# Primary_MCU.net
KiCad netlist of a schematic drawn in Altium Designer
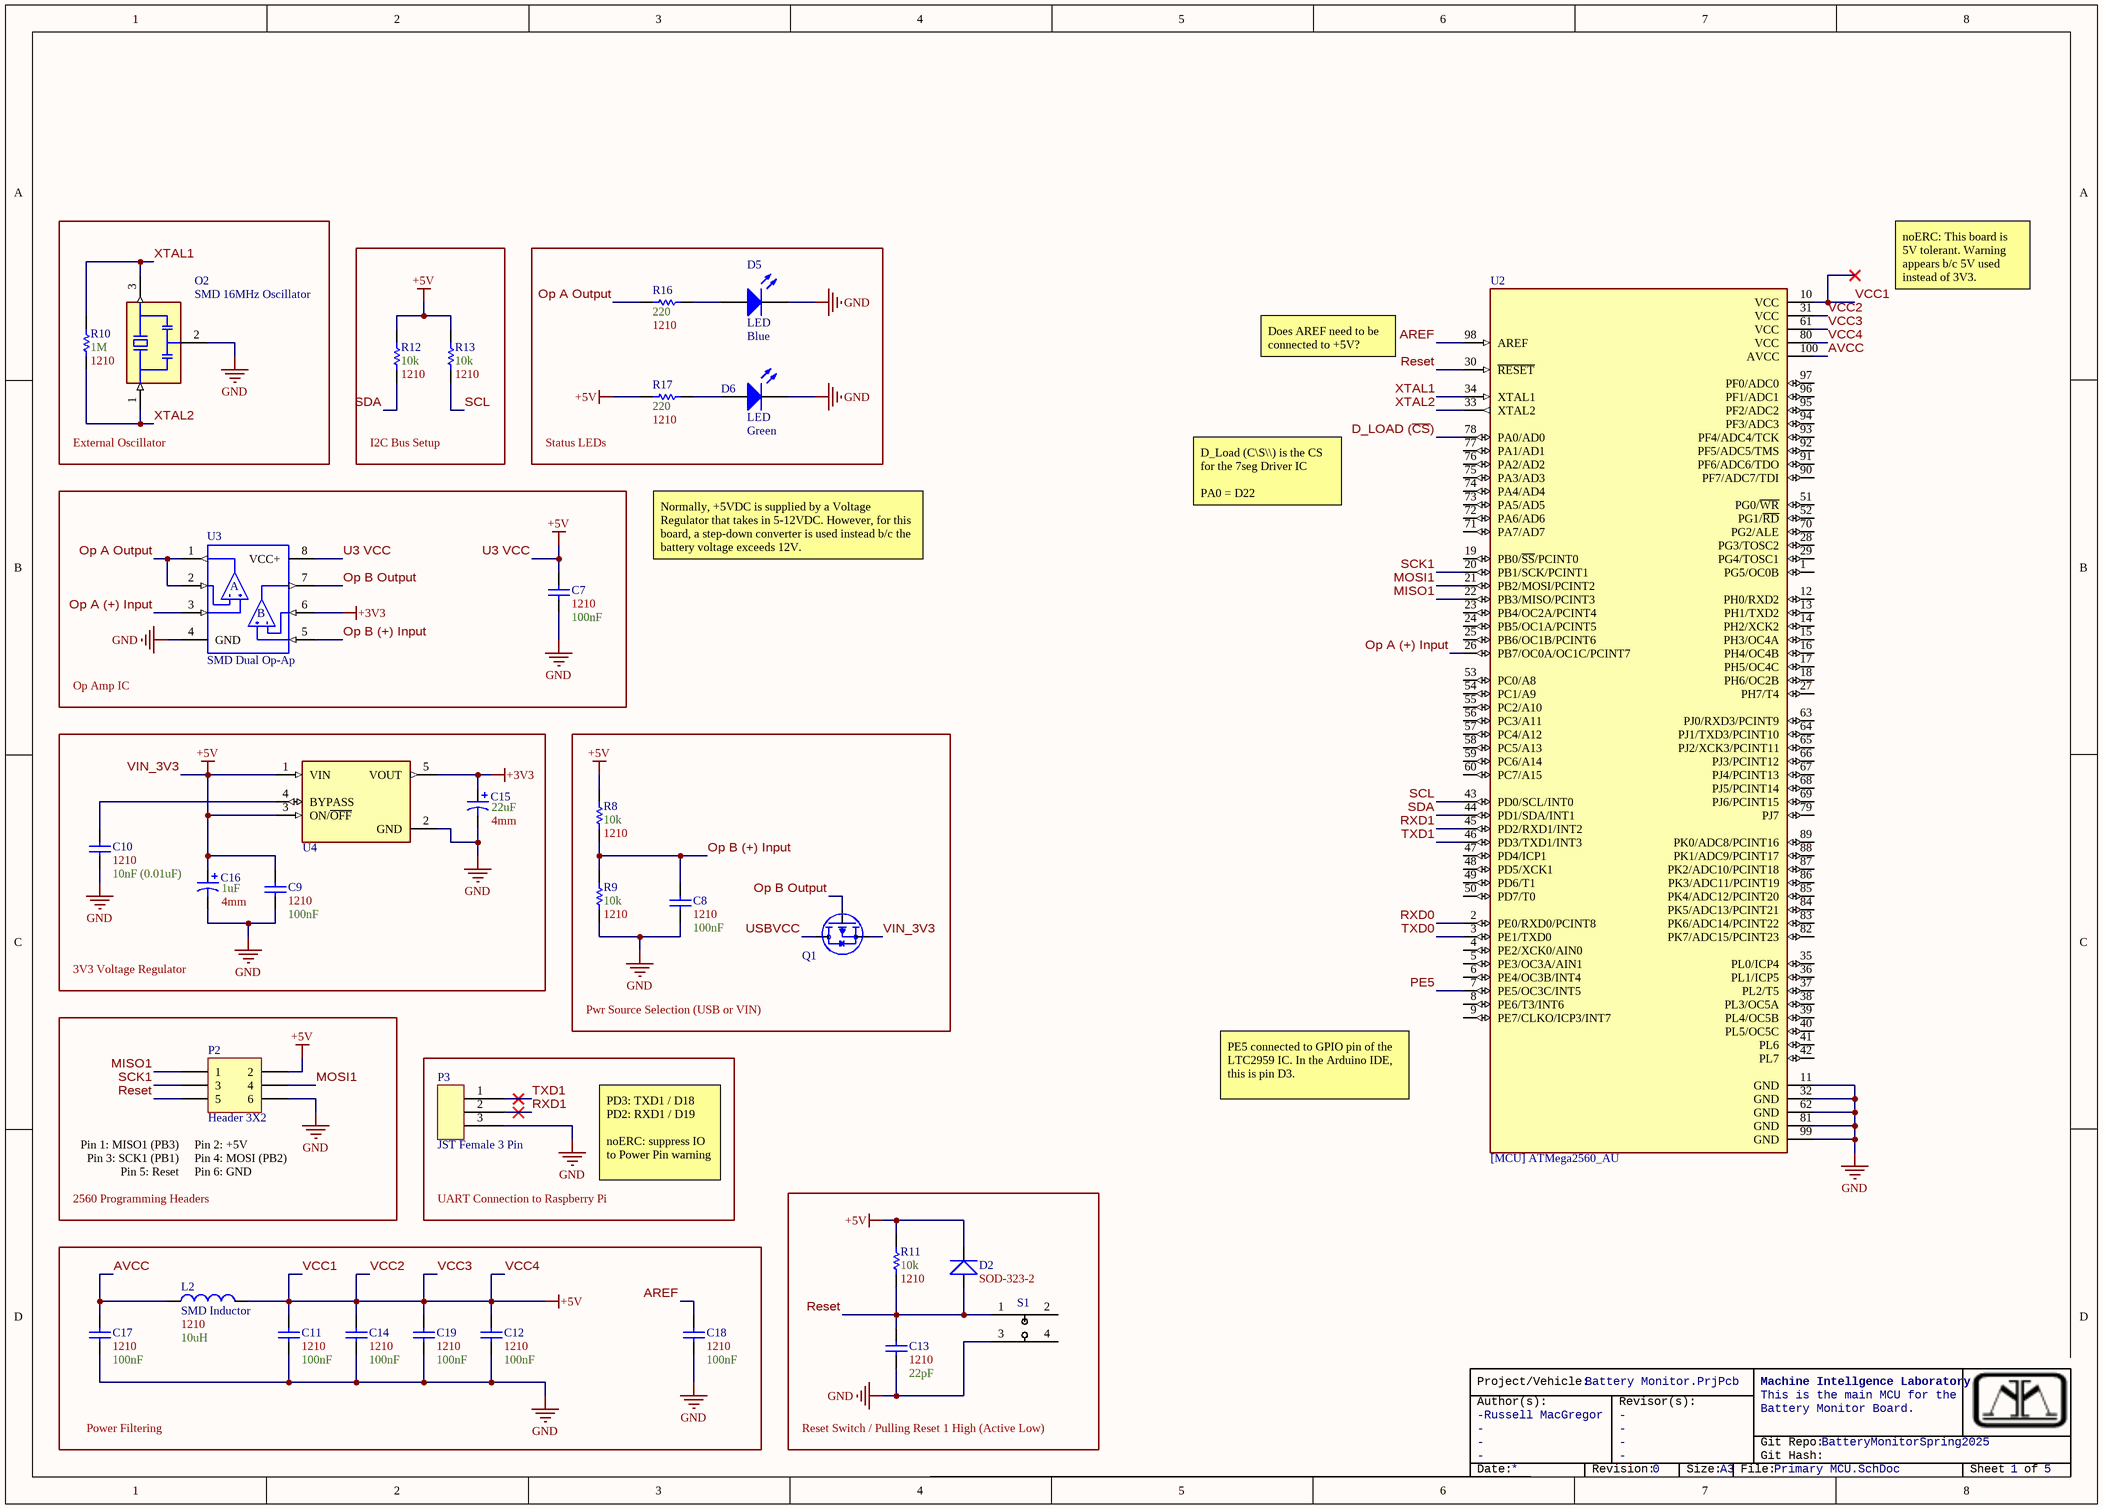
[diagram p0: Primary MCU.SchDoc]

(export (version "E")
  (design (tool "Eeschema 10.0.6"))
  (components
    (comp (ref "C7")
      (value "SMD Cap - Nonpolarized")
      (footprint "SMD Capacitor [1210]")
      (fields
        (field (name "MOUSER PART #") "581-12107C104KAT2A")
        (field (name "SIZE PACKAGE") "1210")
        (field (name "CAPACITANCE") "100nF")
      )
      (libsource (lib "RADM Components") (part "SMD Cap - Nonpolarized"))
    )
    (comp (ref "C8")
      (value "SMD Cap - Nonpolarized")
      (footprint "SMD Capacitor [1210]")
      (fields
        (field (name "MOUSER PART #") "581-12107C104KAT2A")
        (field (name "SIZE PACKAGE") "1210")
        (field (name "CAPACITANCE") "100nF")
      )
      (libsource (lib "RADM Components") (part "SMD Cap - Nonpolarized"))
    )
    (comp (ref "C9")
      (value "SMD Cap - Nonpolarized")
      (footprint "SMD Capacitor [1210]")
      (fields
        (field (name "MOUSER PART #") "581-12107C104KAT2A")
        (field (name "SIZE PACKAGE") "1210")
        (field (name "CAPACITANCE") "100nF")
      )
      (libsource (lib "RADM Components") (part "SMD Cap - Nonpolarized"))
    )
    (comp (ref "C10")
      (value "SMD Cap - Nonpolarized")
      (footprint "SMD Capacitor [1210]")
      (fields
        (field (name "MOUSER PART #") "810-CGA6P1C0G3B103G2")
        (field (name "SIZE PACKAGE") "1210")
        (field (name "CAPACITANCE") "10nF (0.01uF)")
      )
      (libsource (lib "RADM Components") (part "SMD Cap - Nonpolarized"))
    )
    (comp (ref "C11")
      (value "SMD Cap - Nonpolarized")
      (footprint "SMD Capacitor [1210]")
      (fields
        (field (name "MOUSER PART #") "581-12107C104KAT2A")
        (field (name "SIZE PACKAGE") "1210")
        (field (name "CAPACITANCE") "100nF")
      )
      (libsource (lib "RADM Components") (part "SMD Cap - Nonpolarized"))
    )
    (comp (ref "C12")
      (value "SMD Cap - Nonpolarized")
      (footprint "SMD Capacitor [1210]")
      (fields
        (field (name "MOUSER PART #") "581-12107C104KAT2A")
        (field (name "SIZE PACKAGE") "1210")
        (field (name "CAPACITANCE") "100nF")
      )
      (libsource (lib "RADM Components") (part "SMD Cap - Nonpolarized"))
    )
    (comp (ref "C13")
      (value "SMD Cap - Nonpolarized")
      (footprint "SMD Capacitor [1210]")
      (fields
        (field (name "MOUSER PART #") "77-VJ1210A220JXGAT5Z")
        (field (name "SIZE PACKAGE") "1210")
        (field (name "CAPACITANCE") "22pF")
      )
      (libsource (lib "RADM Components") (part "SMD Cap - Nonpolarized"))
    )
    (comp (ref "C14")
      (value "SMD Cap - Nonpolarized")
      (footprint "SMD Capacitor [1210]")
      (fields
        (field (name "MOUSER PART #") "581-12107C104KAT2A")
        (field (name "SIZE PACKAGE") "1210")
        (field (name "CAPACITANCE") "100nF")
      )
      (libsource (lib "RADM Components") (part "SMD Cap - Nonpolarized"))
    )
    (comp (ref "C15")
      (value "SMD Cap - Polarized")
      (footprint "SMD Cap - Polarized, 4mm")
      (description "Diameter: 4mm")
      (fields
        (field (name "MOUSER PART #") "667-EEE-FN1C220R")
        (field (name "CAPACITANCE") "22uF")
        (field (name "DIAMETER") "4mm")
      )
      (libsource (lib "RADM Components") (part "SMD Cap - Polarized"))
    )
    (comp (ref "C16")
      (value "SMD Cap - Polarized")
      (footprint "SMD Cap - Polarized, 4mm")
      (description "Diameter: 4mm")
      (fields
        (field (name "MOUSER PART #") "80-EXV105M050A9BAA")
        (field (name "CAPACITANCE") "1uF")
        (field (name "DIAMETER") "4mm")
      )
      (libsource (lib "RADM Components") (part "SMD Cap - Polarized"))
    )
    (comp (ref "C17")
      (value "SMD Cap - Nonpolarized")
      (footprint "SMD Capacitor [1210]")
      (fields
        (field (name "MOUSER PART #") "581-12107C104KAT2A")
        (field (name "SIZE PACKAGE") "1210")
        (field (name "CAPACITANCE") "100nF")
      )
      (libsource (lib "RADM Components") (part "SMD Cap - Nonpolarized"))
    )
    (comp (ref "C18")
      (value "SMD Cap - Nonpolarized")
      (footprint "SMD Capacitor [1210]")
      (fields
        (field (name "MOUSER PART #") "581-12107C104KAT2A")
        (field (name "SIZE PACKAGE") "1210")
        (field (name "CAPACITANCE") "100nF")
      )
      (libsource (lib "RADM Components") (part "SMD Cap - Nonpolarized"))
    )
    (comp (ref "C19")
      (value "SMD Cap - Nonpolarized")
      (footprint "SMD Capacitor [1210]")
      (fields
        (field (name "MOUSER PART #") "581-12107C104KAT2A")
        (field (name "SIZE PACKAGE") "1210")
        (field (name "CAPACITANCE") "100nF")
      )
      (libsource (lib "RADM Components") (part "SMD Cap - Nonpolarized"))
    )
    (comp (ref "D2")
      (value "SMD Diode")
      (footprint "SMD Diode [SOD-323-2]")
      (description "Part #: CD1206-S01575")
      (fields (field (name "JLC PART #") "C75465") (field (name "SIZE PACKAGE") "SOD-323-2"))
      (libsource (lib "RADM Components") (part "SMD Diode"))
    )
    (comp (ref "D5")
      (value "LED")
      (footprint "LED [3mm, Blue]")
      (description "3mm LED")
      (fields (field (name "COLOR") "Blue"))
      (libsource (lib "RADM Components") (part "LED [3mm]"))
    )
    (comp (ref "D6")
      (value "LED")
      (footprint "Small Green LED")
      (description "3mm LED")
      (fields (field (name "COLOR") "Green"))
      (libsource (lib "RADM Components") (part "Small LED"))
    )
    (comp (ref "L2")
      (value "SMD Inductor")
      (footprint "SMD Inductor [0603]")
      (fields (field (name "SIZE PACKAGE") "1210") (field (name "INDUCTANCE") "10uH"))
      (libsource (lib "RADM Components") (part "SMD Inductor"))
    )
    (comp (ref "O2")
      (value "SMD 16MHz Oscillator")
      (footprint "SMD 16MHz Oscillator [1]")
      (description "Part #: CSTNE16M0V530000R0\r\nJLC Part #: C341521")
      (fields (field (name "JLC PART #") "C341521"))
      (libsource (lib "RADM Components") (part "SMD 16MHz Oscillator [1]"))
    )
    (comp (ref "P2")
      (value "Header 3X2")
      (footprint "HDR2X3")
      (description "Header, 3-Pin, Dual row")
      (fields (field (name "PUBLISHER") "Altium Limited"))
      (libsource (lib "Miscellaneous Connectors") (part "Header 3X2"))
    )
    (comp (ref "P3")
      (value "JST Female 3 Pin")
      (footprint "Jst Female 3pin")
      (libsource (lib "RADM Components") (part "JST Female 3 Pin"))
    )
    (comp (ref "Q1")
      (value "SMD Mosfet (Part #: PMV48XP)")
      (footprint "SMD Mosfet (Part #: PMV48XP)")
      (description "JLC Part #: C2959854")
      (fields (field (name "JLC PART #") "C2959854"))
      (libsource (lib "RADM Components") (part "SMD Mosfet (Part #{colon} PMV48XP)"))
    )
    (comp (ref "R8")
      (value "SMD Resistor")
      (footprint "SMD Resistor [1210]")
      (description "JLC Part #: C728401\r\n(for 1M Ohm Res)")
      (fields
        (field (name "MOUSER PART #") "71-CRCW121010K0JNAIF")
        (field (name "RESISTANCE") "10k")
        (field (name "SIZE PACKAGE") "1210")
      )
      (libsource (lib "RADM Components") (part "SMD Resistor"))
    )
    (comp (ref "R9")
      (value "SMD Resistor")
      (footprint "SMD Resistor [1210]")
      (description "JLC Part #: C728401\r\n(for 1M Ohm Res)")
      (fields
        (field (name "MOUSER PART #") "71-CRCW121010K0JNAIF")
        (field (name "RESISTANCE") "10k")
        (field (name "SIZE PACKAGE") "1210")
      )
      (libsource (lib "RADM Components") (part "SMD Resistor"))
    )
    (comp (ref "R10")
      (value "SMD Resistor")
      (footprint "SMD Resistor [1210]")
      (fields
        (field (name "MOUSER PART #") "71-CRCW12101M00FKEAH")
        (field (name "RESISTANCE") "1M")
        (field (name "SIZE PACKAGE") "1210")
      )
      (libsource (lib "RADM Components") (part "SMD Resistor"))
    )
    (comp (ref "R11")
      (value "SMD Resistor")
      (footprint "SMD Resistor [1210]")
      (description "JLC Part #: C728401\r\n(for 1M Ohm Res)")
      (fields
        (field (name "MOUSER PART #") "71-CRCW121010K0JNAIF")
        (field (name "RESISTANCE") "10k")
        (field (name "SIZE PACKAGE") "1210")
      )
      (libsource (lib "RADM Components") (part "SMD Resistor"))
    )
    (comp (ref "R12")
      (value "SMD Resistor")
      (footprint "SMD Resistor [1210]")
      (fields
        (field (name "MOUSER PART #") "71-CRCW121010K0JNAIF")
        (field (name "RESISTANCE") "10k")
        (field (name "SIZE PACKAGE") "1210")
      )
      (libsource (lib "RADM Components") (part "SMD Resistor"))
    )
    (comp (ref "R13")
      (value "SMD Resistor")
      (footprint "SMD Resistor [1210]")
      (description "JLC Part #: C728401\r\n(for 1M Ohm Res)")
      (fields
        (field (name "MOUSER PART #") "71-CRCW121010K0JNAIF")
        (field (name "RESISTANCE") "10k")
        (field (name "SIZE PACKAGE") "1210")
      )
      (libsource (lib "RADM Components") (part "SMD Resistor"))
    )
    (comp (ref "R16")
      (value "SMD Resistor")
      (footprint "SMD Resistor [1210]")
      (description "JLC Part #: C728401\r\n(for 1M Ohm Res)")
      (fields
        (field (name "MOUSER PART #") "71-CRCW1210220RJNEAH")
        (field (name "RESISTANCE") "220")
        (field (name "SIZE PACKAGE") "1210")
      )
      (libsource (lib "RADM Components") (part "SMD Resistor"))
    )
    (comp (ref "R17")
      (value "SMD Resistor")
      (footprint "SMD Resistor [1210]")
      (description "JLC Part #: C728401\r\n(for 1M Ohm Res)")
      (fields
        (field (name "MOUSER PART #") "71-CRCW1210220RJNEAH")
        (field (name "RESISTANCE") "220")
        (field (name "SIZE PACKAGE") "1210")
      )
      (libsource (lib "RADM Components") (part "SMD Resistor"))
    )
    (comp (ref "S1")
      (value "Thru-Hole Pushbutton")
      (footprint "Thru-Hole Pushbutton")
      (description "Tactile 4pin SPST Pushbutton\r\n(what I expect is a regular pushbutton)")
      (libsource (lib "RADM Components") (part "Thru-Hole Pushbutton"))
    )
    (comp (ref "U2")
      (value "[MCU] ATMega2560_AU")
      (footprint "SMD ATMega2560_AU")
      (description "JLC Part #: C22460")
      (fields (field (name "JLC PART #") "C22460"))
      (libsource (lib "RADM Components") (part "[MCU] ATMega2560_AU"))
    )
    (comp (ref "U3")
      (value "SMD Dual Op-Ap")
      (footprint "SMD Dual Op-Ap (LMV358IDGKR)")
      (description "Part #: LMV358IDGKR")
      (fields (field (name "JLC PART #") "C105242"))
      (libsource (lib "RADM Components") (part "SMD Dual Op-Ap"))
    )
    (comp (ref "U4")
      (value "SMD 3V3 Regulator")
      (footprint "SMD 3V3 Regulator")
      (description "Part #: LP2985-33DBVR\r\nJLC Part #: C95414")
      (fields (field (name "JLC PART #") "C95414") (field (name "MOUSER PART #") "595-LP2985-33DBVR"))
      (libsource (lib "RADM Components") (part "SMD 3V3 Regulator"))
    )
  )
  (nets
    (net (code "1") (name "+3V3") (class "Default")
      (node (ref "C15") (pin "1") (pinfunction "1_1") (pintype "passive"))
      (node (ref "U3") (pin "6") (pinfunction "2IN-_6") (pintype "input"))
      (node (ref "U4") (pin "5") (pinfunction "VOUT_5") (pintype "output"))
    )
    (net (code "2") (name "+5V") (class "Default")
      (node (ref "C11") (pin "2") (pinfunction "2_2") (pintype "passive"))
      (node (ref "C12") (pin "2") (pinfunction "2_2") (pintype "passive"))
      (node (ref "C14") (pin "2") (pinfunction "2_2") (pintype "passive"))
      (node (ref "C16") (pin "1") (pinfunction "1_1") (pintype "passive"))
      (node (ref "C19") (pin "2") (pinfunction "2_2") (pintype "passive"))
      (node (ref "C7") (pin "2") (pinfunction "2_2") (pintype "passive"))
      (node (ref "C9") (pin "2") (pinfunction "2_2") (pintype "passive"))
      (node (ref "D2") (pin "C") (pinfunction "C_C") (pintype "power_in"))
      (node (ref "L2") (pin "2") (pinfunction "2_2") (pintype "passive"))
      (node (ref "P2") (pin "2") (pinfunction "2_2") (pintype "passive"))
      (node (ref "Q1") (pin "2") (pinfunction "S_2") (pintype "passive"))
      (node (ref "R11") (pin "2") (pinfunction "2_2") (pintype "passive"))
      (node (ref "R12") (pin "2") (pinfunction "2_2") (pintype "passive"))
      (node (ref "R13") (pin "2") (pinfunction "2_2") (pintype "passive"))
      (node (ref "R17") (pin "2") (pinfunction "2_2") (pintype "passive"))
      (node (ref "R8") (pin "2") (pinfunction "2_2") (pintype "passive"))
      (node (ref "U2") (pin "10") (pinfunction "VCC_10") (pintype "power_in"))
      (node (ref "U2") (pin "31") (pinfunction "VCC_31") (pintype "power_in"))
      (node (ref "U2") (pin "61") (pinfunction "VCC_61") (pintype "power_in"))
      (node (ref "U2") (pin "80") (pinfunction "VCC_80") (pintype "power_in"))
      (node (ref "U3") (pin "8") (pinfunction "VCC+_8") (pintype "power_in"))
      (node (ref "U4") (pin "1") (pinfunction "VIN_1") (pintype "input"))
      (node (ref "U4") (pin "3") (pinfunction "ON/~{OFF}_3") (pintype "input"))
    )
    (net (code "3") (name "/AREF") (class "Default")
      (node (ref "C18") (pin "2") (pinfunction "2_2") (pintype "passive"))
      (node (ref "U2") (pin "98") (pinfunction "AREF_98") (pintype "input"))
    )
    (net (code "4") (name "/AVCC") (class "Default")
      (node (ref "C17") (pin "2") (pinfunction "2_2") (pintype "passive"))
      (node (ref "L2") (pin "1") (pinfunction "1_1") (pintype "passive"))
      (node (ref "U2") (pin "100") (pinfunction "AVCC_100") (pintype "power_in"))
    )
    (net (code "5") (name "/D_LOAD (~{CS})") (class "Default")
      (node (ref "U2") (pin "78") (pinfunction "PA0/AD0_78") (pintype "bidirectional"))
    )
    (net (code "6") (name "/MISO1") (class "Default")
      (node (ref "P2") (pin "1") (pinfunction "1_1") (pintype "passive"))
      (node (ref "U2") (pin "22") (pinfunction "PB3/MISO/PCINT3_22") (pintype "bidirectional"))
    )
    (net (code "7") (name "/MOSI1") (class "Default")
      (node (ref "P2") (pin "4") (pinfunction "4_4") (pintype "passive"))
      (node (ref "U2") (pin "21") (pinfunction "PB2/MOSI/PCINT2_21") (pintype "bidirectional"))
    )
    (net (code "8") (name "/Op A (+) Input") (class "Default")
      (node (ref "U2") (pin "26") (pinfunction "PB7/OC0A/OC1C/PCINT7_26") (pintype "bidirectional"))
      (node (ref "U3") (pin "3") (pinfunction "1IN+_3") (pintype "input"))
    )
    (net (code "9") (name "/Op A Output") (class "Default")
      (node (ref "R16") (pin "2") (pinfunction "2_2") (pintype "passive"))
      (node (ref "U3") (pin "1") (pinfunction "1OUT_1") (pintype "output"))
      (node (ref "U3") (pin "2") (pinfunction "1IN-_2") (pintype "input"))
    )
    (net (code "10") (name "/Op B (+) Input") (class "Default")
      (node (ref "C8") (pin "2") (pinfunction "2_2") (pintype "passive"))
      (node (ref "R8") (pin "1") (pinfunction "1_1") (pintype "passive"))
      (node (ref "R9") (pin "2") (pinfunction "2_2") (pintype "passive"))
      (node (ref "U3") (pin "5") (pinfunction "2IN+_5") (pintype "input"))
    )
    (net (code "11") (name "/Op B Output") (class "Default")
      (node (ref "Q1") (pin "1") (pinfunction "G_1") (pintype "passive"))
      (node (ref "U3") (pin "7") (pinfunction "2OUT_7") (pintype "output"))
    )
    (net (code "12") (name "/PE5") (class "Default")
      (node (ref "U2") (pin "7") (pinfunction "PE5/OC3C/INT5_7") (pintype "bidirectional"))
    )
    (net (code "13") (name "/RXD0") (class "Default")
      (node (ref "U2") (pin "2") (pinfunction "PE0/RXD0/PCINT8_2") (pintype "bidirectional"))
    )
    (net (code "14") (name "/RXD1") (class "Default")
      (node (ref "P3") (pin "2") (pintype "power_in"))
      (node (ref "U2") (pin "45") (pinfunction "PD2/RXD1/INT2_45") (pintype "bidirectional"))
    )
    (net (code "15") (name "/Reset") (class "Default")
      (node (ref "C13") (pin "2") (pinfunction "2_2") (pintype "passive"))
      (node (ref "D2") (pin "A") (pinfunction "A_A") (pintype "power_in"))
      (node (ref "P2") (pin "5") (pinfunction "5_5") (pintype "passive"))
      (node (ref "R11") (pin "1") (pinfunction "1_1") (pintype "passive"))
      (node (ref "S1") (pin "1") (pintype "power_in"))
      (node (ref "U2") (pin "30") (pinfunction "~{RESET}_30") (pintype "input"))
    )
    (net (code "16") (name "/SCK1") (class "Default")
      (node (ref "P2") (pin "3") (pinfunction "3_3") (pintype "passive"))
      (node (ref "U2") (pin "20") (pinfunction "PB1/SCK/PCINT1_20") (pintype "bidirectional"))
    )
    (net (code "17") (name "/SCL") (class "Default")
      (node (ref "R13") (pin "1") (pinfunction "1_1") (pintype "passive"))
      (node (ref "U2") (pin "43") (pinfunction "PD0/SCL/INT0_43") (pintype "bidirectional"))
    )
    (net (code "18") (name "/SDA") (class "Default")
      (node (ref "R12") (pin "1") (pinfunction "1_1") (pintype "passive"))
      (node (ref "U2") (pin "44") (pinfunction "PD1/SDA/INT1_44") (pintype "bidirectional"))
    )
    (net (code "19") (name "/TXD0") (class "Default")
      (node (ref "U2") (pin "3") (pinfunction "PE1/TXD0_3") (pintype "bidirectional"))
    )
    (net (code "20") (name "/TXD1") (class "Default")
      (node (ref "P3") (pin "1") (pintype "power_in"))
      (node (ref "U2") (pin "46") (pinfunction "PD3/TXD1/INT3_46") (pintype "bidirectional"))
    )
    (net (code "21") (name "/USBVCC") (class "Default")
      (node (ref "Q1") (pin "3") (pinfunction "D_3") (pintype "passive"))
    )
    (net (code "22") (name "/XTAL1") (class "Default")
      (node (ref "O2") (pin "3") (pinfunction "OUT_3") (pintype "output"))
      (node (ref "R10") (pin "2") (pinfunction "2_2") (pintype "passive"))
      (node (ref "U2") (pin "34") (pinfunction "XTAL1_34") (pintype "input"))
    )
    (net (code "23") (name "/XTAL2") (class "Default")
      (node (ref "O2") (pin "1") (pinfunction "IN_1") (pintype "input"))
      (node (ref "R10") (pin "1") (pinfunction "1_1") (pintype "passive"))
      (node (ref "U2") (pin "33") (pinfunction "XTAL2_33") (pintype "output"))
    )
    (net (code "24") (name "GND") (class "Default")
      (node (ref "C10") (pin "1") (pinfunction "1_1") (pintype "passive"))
      (node (ref "C11") (pin "1") (pinfunction "1_1") (pintype "passive"))
      (node (ref "C12") (pin "1") (pinfunction "1_1") (pintype "passive"))
      (node (ref "C13") (pin "1") (pinfunction "1_1") (pintype "passive"))
      (node (ref "C14") (pin "1") (pinfunction "1_1") (pintype "passive"))
      (node (ref "C15") (pin "2") (pinfunction "2_2") (pintype "passive"))
      (node (ref "C16") (pin "2") (pinfunction "2_2") (pintype "passive"))
      (node (ref "C17") (pin "1") (pinfunction "1_1") (pintype "passive"))
      (node (ref "C18") (pin "1") (pinfunction "1_1") (pintype "passive"))
      (node (ref "C19") (pin "1") (pinfunction "1_1") (pintype "passive"))
      (node (ref "C7") (pin "1") (pinfunction "1_1") (pintype "passive"))
      (node (ref "C8") (pin "1") (pinfunction "1_1") (pintype "passive"))
      (node (ref "C9") (pin "1") (pinfunction "1_1") (pintype "passive"))
      (node (ref "D5") (pin "2") (pinfunction "K_2") (pintype "passive"))
      (node (ref "D6") (pin "2") (pinfunction "K_2") (pintype "passive"))
      (node (ref "O2") (pin "2") (pinfunction "GND_2") (pintype "power_in"))
      (node (ref "P2") (pin "6") (pinfunction "6_6") (pintype "passive"))
      (node (ref "P3") (pin "3") (pintype "power_in"))
      (node (ref "R9") (pin "1") (pinfunction "1_1") (pintype "passive"))
      (node (ref "S1") (pin "3") (pintype "power_in"))
      (node (ref "U2") (pin "11") (pinfunction "GND_11") (pintype "power_in"))
      (node (ref "U2") (pin "32") (pinfunction "GND_32") (pintype "power_in"))
      (node (ref "U2") (pin "62") (pinfunction "GND_62") (pintype "power_in"))
      (node (ref "U2") (pin "81") (pinfunction "GND_81") (pintype "power_in"))
      (node (ref "U2") (pin "99") (pinfunction "GND_99") (pintype "power_in"))
      (node (ref "U3") (pin "4") (pinfunction "GND_4") (pintype "power_in"))
      (node (ref "U4") (pin "2") (pinfunction "GND_2") (pintype "power_in"))
    )
    (net (code "25") (name "Net-(D5-A)") (class "Default")
      (node (ref "D5") (pin "1") (pinfunction "A_1") (pintype "passive"))
      (node (ref "R16") (pin "1") (pinfunction "1_1") (pintype "passive"))
    )
    (net (code "26") (name "Net-(D6-A)") (class "Default")
      (node (ref "D6") (pin "1") (pinfunction "A_1") (pintype "passive"))
      (node (ref "R17") (pin "1") (pinfunction "1_1") (pintype "passive"))
    )
    (net (code "27") (name "Net-(U4-BYPASS)") (class "Default")
      (node (ref "C10") (pin "2") (pinfunction "2_2") (pintype "passive"))
      (node (ref "U4") (pin "4") (pinfunction "BYPASS_4") (pintype "bidirectional"))
    )
    (net (code "28") (name "unconnected-(S1-Pad2)") (class "Default")
      (node (ref "S1") (pin "2") (pintype "power_in"))
    )
    (net (code "29") (name "unconnected-(S1-Pad4)") (class "Default")
      (node (ref "S1") (pin "4") (pintype "power_in"))
    )
    (net (code "30") (name "unconnected-(U2-PA1{slash}AD1-Pad77)") (class "Default")
      (node (ref "U2") (pin "77") (pinfunction "PA1/AD1_77") (pintype "bidirectional"))
    )
    (net (code "31") (name "unconnected-(U2-PA2{slash}AD2-Pad76)") (class "Default")
      (node (ref "U2") (pin "76") (pinfunction "PA2/AD2_76") (pintype "bidirectional"))
    )
    (net (code "32") (name "unconnected-(U2-PA3{slash}AD3-Pad75)") (class "Default")
      (node (ref "U2") (pin "75") (pinfunction "PA3/AD3_75") (pintype "bidirectional"))
    )
    (net (code "33") (name "unconnected-(U2-PA4{slash}AD4-Pad74)") (class "Default")
      (node (ref "U2") (pin "74") (pinfunction "PA4/AD4_74") (pintype "bidirectional"))
    )
    (net (code "34") (name "unconnected-(U2-PA5{slash}AD5-Pad73)") (class "Default")
      (node (ref "U2") (pin "73") (pinfunction "PA5/AD5_73") (pintype "bidirectional"))
    )
    (net (code "35") (name "unconnected-(U2-PA6{slash}AD6-Pad72)") (class "Default")
      (node (ref "U2") (pin "72") (pinfunction "PA6/AD6_72") (pintype "bidirectional"))
    )
    (net (code "36") (name "unconnected-(U2-PA7{slash}AD7-Pad71)") (class "Default")
      (node (ref "U2") (pin "71") (pinfunction "PA7/AD7_71") (pintype "bidirectional"))
    )
    (net (code "37") (name "unconnected-(U2-PB0{slash}~{SS}{slash}PCINT0-Pad19)") (class "Default")
      (node (ref "U2") (pin "19") (pinfunction "PB0/~{SS}/PCINT0_19") (pintype "bidirectional"))
    )
    (net (code "38") (name "unconnected-(U2-PB4{slash}OC2A{slash}PCINT4-Pad23)") (class "Default")
      (node (ref "U2") (pin "23") (pinfunction "PB4/OC2A/PCINT4_23") (pintype "bidirectional"))
    )
    (net (code "39") (name "unconnected-(U2-PB5{slash}OC1A{slash}PCINT5-Pad24)") (class "Default")
      (node (ref "U2") (pin "24") (pinfunction "PB5/OC1A/PCINT5_24") (pintype "bidirectional"))
    )
    (net (code "40") (name "unconnected-(U2-PB6{slash}OC1B{slash}PCINT6-Pad25)") (class "Default")
      (node (ref "U2") (pin "25") (pinfunction "PB6/OC1B/PCINT6_25") (pintype "bidirectional"))
    )
    (net (code "41") (name "unconnected-(U2-PC0{slash}A8-Pad53)") (class "Default")
      (node (ref "U2") (pin "53") (pinfunction "PC0/A8_53") (pintype "bidirectional"))
    )
    (net (code "42") (name "unconnected-(U2-PC1{slash}A9-Pad54)") (class "Default")
      (node (ref "U2") (pin "54") (pinfunction "PC1/A9_54") (pintype "bidirectional"))
    )
    (net (code "43") (name "unconnected-(U2-PC2{slash}A10-Pad55)") (class "Default")
      (node (ref "U2") (pin "55") (pinfunction "PC2/A10_55") (pintype "bidirectional"))
    )
    (net (code "44") (name "unconnected-(U2-PC3{slash}A11-Pad56)") (class "Default")
      (node (ref "U2") (pin "56") (pinfunction "PC3/A11_56") (pintype "bidirectional"))
    )
    (net (code "45") (name "unconnected-(U2-PC4{slash}A12-Pad57)") (class "Default")
      (node (ref "U2") (pin "57") (pinfunction "PC4/A12_57") (pintype "bidirectional"))
    )
    (net (code "46") (name "unconnected-(U2-PC5{slash}A13-Pad58)") (class "Default")
      (node (ref "U2") (pin "58") (pinfunction "PC5/A13_58") (pintype "bidirectional"))
    )
    (net (code "47") (name "unconnected-(U2-PC6{slash}A14-Pad59)") (class "Default")
      (node (ref "U2") (pin "59") (pinfunction "PC6/A14_59") (pintype "bidirectional"))
    )
    (net (code "48") (name "unconnected-(U2-PC7{slash}A15-Pad60)") (class "Default")
      (node (ref "U2") (pin "60") (pinfunction "PC7/A15_60") (pintype "bidirectional"))
    )
    (net (code "49") (name "unconnected-(U2-PD4{slash}ICP1-Pad47)") (class "Default")
      (node (ref "U2") (pin "47") (pinfunction "PD4/ICP1_47") (pintype "bidirectional"))
    )
    (net (code "50") (name "unconnected-(U2-PD5{slash}XCK1-Pad48)") (class "Default")
      (node (ref "U2") (pin "48") (pinfunction "PD5/XCK1_48") (pintype "bidirectional"))
    )
    (net (code "51") (name "unconnected-(U2-PD6{slash}T1-Pad49)") (class "Default")
      (node (ref "U2") (pin "49") (pinfunction "PD6/T1_49") (pintype "bidirectional"))
    )
    (net (code "52") (name "unconnected-(U2-PD7{slash}T0-Pad50)") (class "Default")
      (node (ref "U2") (pin "50") (pinfunction "PD7/T0_50") (pintype "bidirectional"))
    )
    (net (code "53") (name "unconnected-(U2-PE2{slash}XCK0{slash}AIN0-Pad4)") (class "Default")
      (node (ref "U2") (pin "4") (pinfunction "PE2/XCK0/AIN0_4") (pintype "bidirectional"))
    )
    (net (code "54") (name "unconnected-(U2-PE3{slash}OC3A{slash}AIN1-Pad5)") (class "Default")
      (node (ref "U2") (pin "5") (pinfunction "PE3/OC3A/AIN1_5") (pintype "bidirectional"))
    )
    (net (code "55") (name "unconnected-(U2-PE4{slash}OC3B{slash}INT4-Pad6)") (class "Default")
      (node (ref "U2") (pin "6") (pinfunction "PE4/OC3B/INT4_6") (pintype "bidirectional"))
    )
    (net (code "56") (name "unconnected-(U2-PE6{slash}T3{slash}INT6-Pad8)") (class "Default")
      (node (ref "U2") (pin "8") (pinfunction "PE6/T3/INT6_8") (pintype "bidirectional"))
    )
    (net (code "57") (name "unconnected-(U2-PE7{slash}CLKO{slash}ICP3{slash}INT7-Pad9)") (class "Default")
      (node (ref "U2") (pin "9") (pinfunction "PE7/CLKO/ICP3/INT7_9") (pintype "bidirectional"))
    )
    (net (code "58") (name "unconnected-(U2-PF0{slash}ADC0-Pad97)") (class "Default")
      (node (ref "U2") (pin "97") (pinfunction "PF0/ADC0_97") (pintype "bidirectional"))
    )
    (net (code "59") (name "unconnected-(U2-PF1{slash}ADC1-Pad96)") (class "Default")
      (node (ref "U2") (pin "96") (pinfunction "PF1/ADC1_96") (pintype "bidirectional"))
    )
    (net (code "60") (name "unconnected-(U2-PF2{slash}ADC2-Pad95)") (class "Default")
      (node (ref "U2") (pin "95") (pinfunction "PF2/ADC2_95") (pintype "bidirectional"))
    )
    (net (code "61") (name "unconnected-(U2-PF3{slash}ADC3-Pad94)") (class "Default")
      (node (ref "U2") (pin "94") (pinfunction "PF3/ADC3_94") (pintype "bidirectional"))
    )
    (net (code "62") (name "unconnected-(U2-PF4{slash}ADC4{slash}TCK-Pad93)") (class "Default")
      (node (ref "U2") (pin "93") (pinfunction "PF4/ADC4/TCK_93") (pintype "bidirectional"))
    )
    (net (code "63") (name "unconnected-(U2-PF5{slash}ADC5{slash}TMS-Pad92)") (class "Default")
      (node (ref "U2") (pin "92") (pinfunction "PF5/ADC5/TMS_92") (pintype "bidirectional"))
    )
    (net (code "64") (name "unconnected-(U2-PF6{slash}ADC6{slash}TDO-Pad91)") (class "Default")
      (node (ref "U2") (pin "91") (pinfunction "PF6/ADC6/TDO_91") (pintype "bidirectional"))
    )
    (net (code "65") (name "unconnected-(U2-PF7{slash}ADC7{slash}TDI-Pad90)") (class "Default")
      (node (ref "U2") (pin "90") (pinfunction "PF7/ADC7/TDI_90") (pintype "bidirectional"))
    )
    (net (code "66") (name "unconnected-(U2-PG0{slash}~{WR}-Pad51)") (class "Default")
      (node (ref "U2") (pin "51") (pinfunction "PG0/~{WR}_51") (pintype "bidirectional"))
    )
    (net (code "67") (name "unconnected-(U2-PG1{slash}~{RD}-Pad52)") (class "Default")
      (node (ref "U2") (pin "52") (pinfunction "PG1/~{RD}_52") (pintype "bidirectional"))
    )
    (net (code "68") (name "unconnected-(U2-PG2{slash}ALE-Pad70)") (class "Default")
      (node (ref "U2") (pin "70") (pinfunction "PG2/ALE_70") (pintype "bidirectional"))
    )
    (net (code "69") (name "unconnected-(U2-PG3{slash}TOSC2-Pad28)") (class "Default")
      (node (ref "U2") (pin "28") (pinfunction "PG3/TOSC2_28") (pintype "bidirectional"))
    )
    (net (code "70") (name "unconnected-(U2-PG4{slash}TOSC1-Pad29)") (class "Default")
      (node (ref "U2") (pin "29") (pinfunction "PG4/TOSC1_29") (pintype "bidirectional"))
    )
    (net (code "71") (name "unconnected-(U2-PG5{slash}OC0B-Pad1)") (class "Default")
      (node (ref "U2") (pin "1") (pinfunction "PG5/OC0B_1") (pintype "bidirectional"))
    )
    (net (code "72") (name "unconnected-(U2-PH0{slash}RXD2-Pad12)") (class "Default")
      (node (ref "U2") (pin "12") (pinfunction "PH0/RXD2_12") (pintype "bidirectional"))
    )
    (net (code "73") (name "unconnected-(U2-PH1{slash}TXD2-Pad13)") (class "Default")
      (node (ref "U2") (pin "13") (pinfunction "PH1/TXD2_13") (pintype "bidirectional"))
    )
    (net (code "74") (name "unconnected-(U2-PH2{slash}XCK2-Pad14)") (class "Default")
      (node (ref "U2") (pin "14") (pinfunction "PH2/XCK2_14") (pintype "bidirectional"))
    )
    (net (code "75") (name "unconnected-(U2-PH3{slash}OC4A-Pad15)") (class "Default")
      (node (ref "U2") (pin "15") (pinfunction "PH3/OC4A_15") (pintype "bidirectional"))
    )
    (net (code "76") (name "unconnected-(U2-PH4{slash}OC4B-Pad16)") (class "Default")
      (node (ref "U2") (pin "16") (pinfunction "PH4/OC4B_16") (pintype "bidirectional"))
    )
    (net (code "77") (name "unconnected-(U2-PH5{slash}OC4C-Pad17)") (class "Default")
      (node (ref "U2") (pin "17") (pinfunction "PH5/OC4C_17") (pintype "bidirectional"))
    )
    (net (code "78") (name "unconnected-(U2-PH6{slash}OC2B-Pad18)") (class "Default")
      (node (ref "U2") (pin "18") (pinfunction "PH6/OC2B_18") (pintype "bidirectional"))
    )
    (net (code "79") (name "unconnected-(U2-PH7{slash}T4-Pad27)") (class "Default")
      (node (ref "U2") (pin "27") (pinfunction "PH7/T4_27") (pintype "bidirectional"))
    )
    (net (code "80") (name "unconnected-(U2-PJ0{slash}RXD3{slash}PCINT9-Pad63)") (class "Default")
      (node (ref "U2") (pin "63") (pinfunction "PJ0/RXD3/PCINT9_63") (pintype "bidirectional"))
    )
    (net (code "81") (name "unconnected-(U2-PJ1{slash}TXD3{slash}PCINT10-Pad64)") (class "Default")
      (node (ref "U2") (pin "64") (pinfunction "PJ1/TXD3/PCINT10_64") (pintype "bidirectional"))
    )
    (net (code "82") (name "unconnected-(U2-PJ2{slash}XCK3{slash}PCINT11-Pad65)") (class "Default")
      (node (ref "U2") (pin "65") (pinfunction "PJ2/XCK3/PCINT11_65") (pintype "bidirectional"))
    )
    (net (code "83") (name "unconnected-(U2-PJ3{slash}PCINT12-Pad66)") (class "Default")
      (node (ref "U2") (pin "66") (pinfunction "PJ3/PCINT12_66") (pintype "bidirectional"))
    )
    (net (code "84") (name "unconnected-(U2-PJ4{slash}PCINT13-Pad67)") (class "Default")
      (node (ref "U2") (pin "67") (pinfunction "PJ4/PCINT13_67") (pintype "bidirectional"))
    )
    (net (code "85") (name "unconnected-(U2-PJ5{slash}PCINT14-Pad68)") (class "Default")
      (node (ref "U2") (pin "68") (pinfunction "PJ5/PCINT14_68") (pintype "bidirectional"))
    )
    (net (code "86") (name "unconnected-(U2-PJ6{slash}PCINT15-Pad69)") (class "Default")
      (node (ref "U2") (pin "69") (pinfunction "PJ6/PCINT15_69") (pintype "bidirectional"))
    )
    (net (code "87") (name "unconnected-(U2-PJ7-Pad79)") (class "Default")
      (node (ref "U2") (pin "79") (pinfunction "PJ7_79") (pintype "bidirectional"))
    )
    (net (code "88") (name "unconnected-(U2-PK0{slash}ADC8{slash}PCINT16-Pad89)") (class "Default")
      (node (ref "U2") (pin "89") (pinfunction "PK0/ADC8/PCINT16_89") (pintype "bidirectional"))
    )
    (net (code "89") (name "unconnected-(U2-PK1{slash}ADC9{slash}PCINT17-Pad88)") (class "Default")
      (node (ref "U2") (pin "88") (pinfunction "PK1/ADC9/PCINT17_88") (pintype "bidirectional"))
    )
    (net (code "90") (name "unconnected-(U2-PK2{slash}ADC10{slash}PCINT18-Pad87)") (class "Default")
      (node (ref "U2") (pin "87") (pinfunction "PK2/ADC10/PCINT18_87") (pintype "bidirectional"))
    )
    (net (code "91") (name "unconnected-(U2-PK3{slash}ADC11{slash}PCINT19-Pad86)") (class "Default")
      (node (ref "U2") (pin "86") (pinfunction "PK3/ADC11/PCINT19_86") (pintype "bidirectional"))
    )
    (net (code "92") (name "unconnected-(U2-PK4{slash}ADC12{slash}PCINT20-Pad85)") (class "Default")
      (node (ref "U2") (pin "85") (pinfunction "PK4/ADC12/PCINT20_85") (pintype "bidirectional"))
    )
    (net (code "93") (name "unconnected-(U2-PK5{slash}ADC13{slash}PCINT21-Pad84)") (class "Default")
      (node (ref "U2") (pin "84") (pinfunction "PK5/ADC13/PCINT21_84") (pintype "bidirectional"))
    )
    (net (code "94") (name "unconnected-(U2-PK6{slash}ADC14{slash}PCINT22-Pad83)") (class "Default")
      (node (ref "U2") (pin "83") (pinfunction "PK6/ADC14/PCINT22_83") (pintype "bidirectional"))
    )
    (net (code "95") (name "unconnected-(U2-PK7{slash}ADC15{slash}PCINT23-Pad82)") (class "Default")
      (node (ref "U2") (pin "82") (pinfunction "PK7/ADC15/PCINT23_82") (pintype "bidirectional"))
    )
    (net (code "96") (name "unconnected-(U2-PL0{slash}ICP4-Pad35)") (class "Default")
      (node (ref "U2") (pin "35") (pinfunction "PL0/ICP4_35") (pintype "bidirectional"))
    )
    (net (code "97") (name "unconnected-(U2-PL1{slash}ICP5-Pad36)") (class "Default")
      (node (ref "U2") (pin "36") (pinfunction "PL1/ICP5_36") (pintype "bidirectional"))
    )
    (net (code "98") (name "unconnected-(U2-PL2{slash}T5-Pad37)") (class "Default")
      (node (ref "U2") (pin "37") (pinfunction "PL2/T5_37") (pintype "bidirectional"))
    )
    (net (code "99") (name "unconnected-(U2-PL3{slash}OC5A-Pad38)") (class "Default")
      (node (ref "U2") (pin "38") (pinfunction "PL3/OC5A_38") (pintype "bidirectional"))
    )
    (net (code "100") (name "unconnected-(U2-PL4{slash}OC5B-Pad39)") (class "Default")
      (node (ref "U2") (pin "39") (pinfunction "PL4/OC5B_39") (pintype "bidirectional"))
    )
    (net (code "101") (name "unconnected-(U2-PL5{slash}OC5C-Pad40)") (class "Default")
      (node (ref "U2") (pin "40") (pinfunction "PL5/OC5C_40") (pintype "bidirectional"))
    )
    (net (code "102") (name "unconnected-(U2-PL6-Pad41)") (class "Default")
      (node (ref "U2") (pin "41") (pinfunction "PL6_41") (pintype "bidirectional"))
    )
    (net (code "103") (name "unconnected-(U2-PL7-Pad42)") (class "Default")
      (node (ref "U2") (pin "42") (pinfunction "PL7_42") (pintype "bidirectional"))
    )
  )
)
